# wifistepper.net
KiCad netlist of a schematic drawn in EAGLE
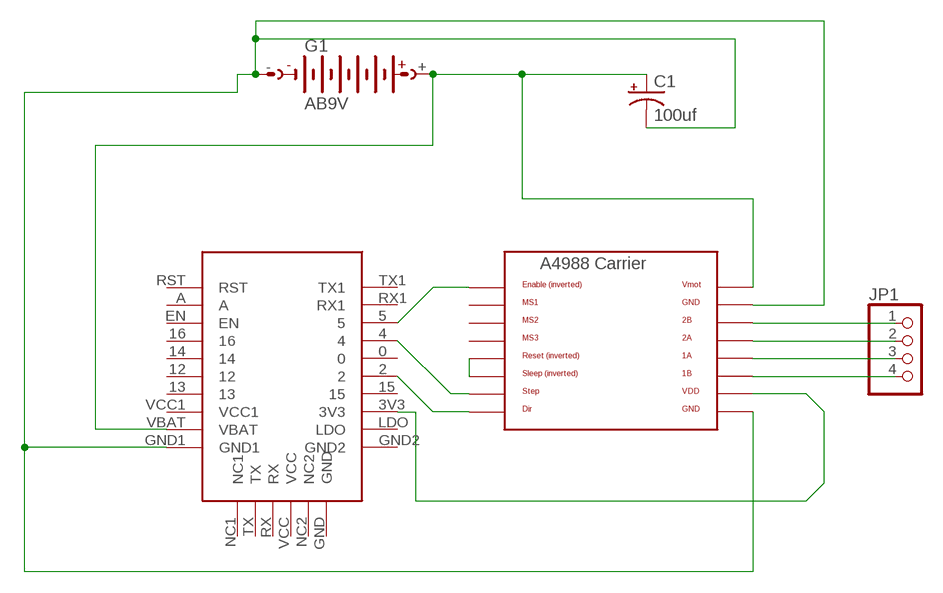
[diagram p0: schematic, sheet 1]

(export (version "E")
  (design (tool "Eeschema 10.0.6"))
  (components
    (comp (ref "C1")
      (value "100uf")
      (footprint "eagle-import:E2,5-6")
      (libsource (lib "eagle-import") (part "CPOL-USE2.5-6"))
    )
    (comp (ref "G1")
      (value "AB9V")
      (footprint "eagle-import:AB9V")
      (libsource (lib "eagle-import") (part "AB9V"))
    )
    (comp (ref "JP1")
      (value "PINHD-1X4")
      (footprint "eagle-import:1X04")
      (libsource (lib "eagle-import") (part "PINHD-1X4"))
    )
    (comp (ref "U$1")
      (value "HUZZAH_BREAKOUT_ESP8266THROUGHHOLE")
      (footprint "eagle-import:HUZZAH_BREAKOUT")
      (libsource (lib "eagle-import") (part "HUZZAH_BREAKOUT_ESP8266THROUGHHOLE"))
    )
    (comp (ref "U$2")
      (value "A4988BREAKOUT")
      (footprint "eagle-import:A4988BREAKOUT")
      (libsource (lib "eagle-import") (part "A4988BREAKOUT"))
    )
  )
  (nets
    (net (code "1") (name "Net-(C1-Pad+)") (class "Default")
      (node (ref "C1") (pin "+") (pinfunction "+_+") (pintype "passive"))
      (node (ref "G1") (pin "+") (pinfunction "+_+") (pintype "passive"))
      (node (ref "U$1") (pin "VBAT") (pinfunction "VBAT_VBAT") (pintype "bidirectional"))
      (node (ref "U$2") (pin "VMOT") (pinfunction "VMOT_VMOT") (pintype "power_in"))
    )
    (net (code "2") (name "Net-(C1-Pad-)") (class "Default")
      (node (ref "C1") (pin "-") (pinfunction "-_-") (pintype "passive"))
      (node (ref "G1") (pin "-") (pinfunction "-_-") (pintype "passive"))
      (node (ref "U$1") (pin "GND1") (pinfunction "GND1_GND1") (pintype "bidirectional"))
      (node (ref "U$2") (pin "GND") (pinfunction "GND_GND") (pintype "power_in"))
      (node (ref "U$2") (pin "GND@0") (pinfunction "GND_GND@0") (pintype "power_in"))
    )
    (net (code "3") (name "Net-(JP1-Pad1)") (class "Default")
      (node (ref "JP1") (pin "1") (pinfunction "1_1") (pintype "passive"))
      (node (ref "U$2") (pin "2B") (pinfunction "2B_2B") (pintype "output"))
    )
    (net (code "4") (name "Net-(JP1-Pad2)") (class "Default")
      (node (ref "JP1") (pin "2") (pinfunction "2_2") (pintype "passive"))
      (node (ref "U$2") (pin "2A") (pinfunction "2A_2A") (pintype "output"))
    )
    (net (code "5") (name "Net-(JP1-Pad3)") (class "Default")
      (node (ref "JP1") (pin "3") (pinfunction "3_3") (pintype "passive"))
      (node (ref "U$2") (pin "1A") (pinfunction "1A_1A") (pintype "output"))
    )
    (net (code "6") (name "Net-(JP1-Pad4)") (class "Default")
      (node (ref "JP1") (pin "4") (pinfunction "4_4") (pintype "passive"))
      (node (ref "U$2") (pin "1B") (pinfunction "1B_1B") (pintype "output"))
    )
    (net (code "7") (name "Net-(U$1-Pad2)") (class "Default")
      (node (ref "U$1") (pin "2") (pinfunction "2_2") (pintype "bidirectional"))
      (node (ref "U$2") (pin "DIR") (pinfunction "DIR_DIR") (pintype "input"))
    )
    (net (code "8") (name "Net-(U$1-Pad3V3)") (class "Default")
      (node (ref "U$1") (pin "3V3") (pinfunction "3V3_3V3") (pintype "bidirectional"))
      (node (ref "U$2") (pin "VDD") (pinfunction "VDD_VDD") (pintype "power_in"))
    )
    (net (code "9") (name "Net-(U$1-Pad4)") (class "Default")
      (node (ref "U$1") (pin "4") (pinfunction "4_4") (pintype "bidirectional"))
      (node (ref "U$2") (pin "STEP") (pinfunction "STEP_STEP") (pintype "input"))
    )
    (net (code "10") (name "Net-(U$1-Pad5)") (class "Default")
      (node (ref "U$1") (pin "5") (pinfunction "5_5") (pintype "bidirectional"))
      (node (ref "U$2") (pin "EN") (pinfunction "EN_EN") (pintype "input"))
    )
    (net (code "11") (name "Net-(U$2-SLEEP)") (class "Default")
      (node (ref "U$2") (pin "RST") (pinfunction "RST_RST") (pintype "input"))
      (node (ref "U$2") (pin "SLP") (pinfunction "SLEEP_SLP") (pintype "input"))
    )
    (net (code "12") (name "unconnected-(U$1-Pad0)") (class "Default")
      (node (ref "U$1") (pin "0") (pinfunction "0_0") (pintype "bidirectional"))
    )
    (net (code "13") (name "unconnected-(U$1-Pad12)") (class "Default")
      (node (ref "U$1") (pin "12") (pinfunction "12_12") (pintype "bidirectional"))
    )
    (net (code "14") (name "unconnected-(U$1-Pad13)") (class "Default")
      (node (ref "U$1") (pin "13") (pinfunction "13_13") (pintype "bidirectional"))
    )
    (net (code "15") (name "unconnected-(U$1-Pad14)") (class "Default")
      (node (ref "U$1") (pin "14") (pinfunction "14_14") (pintype "bidirectional"))
    )
    (net (code "16") (name "unconnected-(U$1-Pad15)") (class "Default")
      (node (ref "U$1") (pin "15") (pinfunction "15_15") (pintype "bidirectional"))
    )
    (net (code "17") (name "unconnected-(U$1-Pad16)") (class "Default")
      (node (ref "U$1") (pin "16") (pinfunction "16_16") (pintype "bidirectional"))
    )
    (net (code "18") (name "unconnected-(U$1-PadA)") (class "Default")
      (node (ref "U$1") (pin "A") (pinfunction "A_A") (pintype "bidirectional"))
    )
    (net (code "19") (name "unconnected-(U$1-PadEN)") (class "Default")
      (node (ref "U$1") (pin "EN") (pinfunction "EN_EN") (pintype "bidirectional"))
    )
    (net (code "20") (name "unconnected-(U$1-PadGND)") (class "Default")
      (node (ref "U$1") (pin "GND") (pinfunction "GND_GND") (pintype "bidirectional"))
    )
    (net (code "21") (name "unconnected-(U$1-PadGND2)") (class "Default")
      (node (ref "U$1") (pin "GND2") (pinfunction "GND2_GND2") (pintype "bidirectional"))
    )
    (net (code "22") (name "unconnected-(U$1-PadLDO)") (class "Default")
      (node (ref "U$1") (pin "LDO") (pinfunction "LDO_LDO") (pintype "bidirectional"))
    )
    (net (code "23") (name "unconnected-(U$1-PadNC1)") (class "Default")
      (node (ref "U$1") (pin "NC1") (pinfunction "NC1_NC1") (pintype "bidirectional"))
    )
    (net (code "24") (name "unconnected-(U$1-PadNC2)") (class "Default")
      (node (ref "U$1") (pin "NC2") (pinfunction "NC2_NC2") (pintype "bidirectional"))
    )
    (net (code "25") (name "unconnected-(U$1-PadRST)") (class "Default")
      (node (ref "U$1") (pin "RST") (pinfunction "RST_RST") (pintype "bidirectional"))
    )
    (net (code "26") (name "unconnected-(U$1-PadRX)") (class "Default")
      (node (ref "U$1") (pin "RX") (pinfunction "RX_RX") (pintype "bidirectional"))
    )
    (net (code "27") (name "unconnected-(U$1-PadRX1)") (class "Default")
      (node (ref "U$1") (pin "RX1") (pinfunction "RX1_RX1") (pintype "bidirectional"))
    )
    (net (code "28") (name "unconnected-(U$1-PadTX)") (class "Default")
      (node (ref "U$1") (pin "TX") (pinfunction "TX_TX") (pintype "bidirectional"))
    )
    (net (code "29") (name "unconnected-(U$1-PadTX1)") (class "Default")
      (node (ref "U$1") (pin "TX1") (pinfunction "TX1_TX1") (pintype "bidirectional"))
    )
    (net (code "30") (name "unconnected-(U$1-PadVCC)") (class "Default")
      (node (ref "U$1") (pin "VCC") (pinfunction "VCC_VCC") (pintype "bidirectional"))
    )
    (net (code "31") (name "unconnected-(U$1-PadVCC1)") (class "Default")
      (node (ref "U$1") (pin "VCC1") (pinfunction "VCC1_VCC1") (pintype "bidirectional"))
    )
    (net (code "32") (name "unconnected-(U$2-PadMS1)") (class "Default")
      (node (ref "U$2") (pin "MS1") (pinfunction "MS1_MS1") (pintype "input"))
    )
    (net (code "33") (name "unconnected-(U$2-PadMS2)") (class "Default")
      (node (ref "U$2") (pin "MS2") (pinfunction "MS2_MS2") (pintype "input"))
    )
    (net (code "34") (name "unconnected-(U$2-PadMS3)") (class "Default")
      (node (ref "U$2") (pin "MS3") (pinfunction "MS3_MS3") (pintype "input"))
    )
  )
)
